# 5VRegulator.net
KiCad netlist of a schematic drawn in Altium Designer
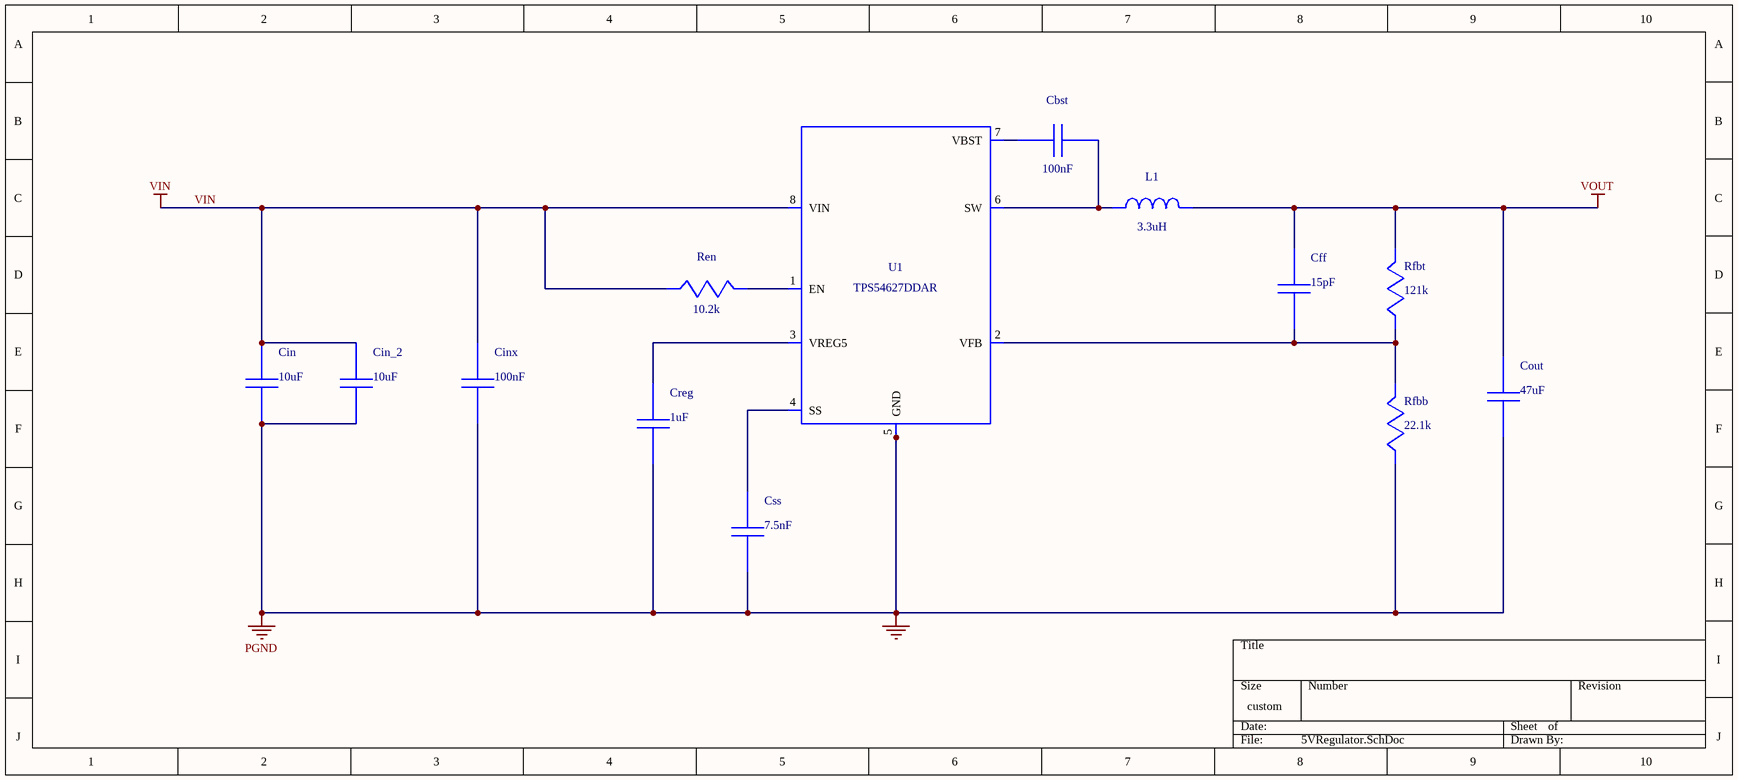
[diagram p0: 5VRegulator.SchDoc]

(export (version "E")
  (design (tool "Eeschema 10.0.6"))
  (components
    (comp (ref "Cbst")
      (value "100nF")
      (description "06033C104KAT2A")
      (libsource (lib "TI WEBENCH") (part "Cbst"))
    )
    (comp (ref "Cff")
      (value "15pF")
      (description "C0603C150M8GACTU")
      (libsource (lib "TI WEBENCH") (part "Cff"))
    )
    (comp (ref "Cin")
      (value "10uF")
      (description "GRM31CR71E106KA1")
      (fields (field (name "MANUFACTURER PART NUMBER") "GRM31CR71E106KA12L"))
      (libsource (lib "TI WEBENCH") (part "Cin"))
    )
    (comp (ref "Cinx")
      (value "100nF")
      (description "06033C104KAT2A")
      (libsource (lib "TI WEBENCH") (part "Cinx"))
    )
    (comp (ref "Cin_2")
      (value "10uF")
      (description "GRM31CR71E106KA1")
      (fields (field (name "MANUFACTURER PART NUMBER") "GRM31CR71E106KA12L"))
      (libsource (lib "TI WEBENCH") (part "Cin_2"))
    )
    (comp (ref "Cout")
      (value "47uF")
      (description "GRM31CR61A476KE1")
      (fields (field (name "MANUFACTURER PART NUMBER") "GRM31CR61A476KE15L"))
      (libsource (lib "TI WEBENCH") (part "Cout"))
    )
    (comp (ref "Creg")
      (value "1uF")
      (description "C0603C105Z8VACTU")
      (libsource (lib "TI WEBENCH") (part "Creg"))
    )
    (comp (ref "Css")
      (value "7.5nF")
      (description "C0603C752J3GAC78")
      (fields (field (name "MANUFACTURER PART NUMBER") "C0603C752J3GAC7867"))
      (libsource (lib "TI WEBENCH") (part "Css"))
    )
    (comp (ref "L1") (value "3.3uH") (description "SRP1040-3R3M") (libsource (lib "TI WEBENCH") (part "L1")))
    (comp (ref "Ren")
      (value "10.2k")
      (description "CRCW040210K2FKED")
      (libsource (lib "TI WEBENCH") (part "Ren"))
    )
    (comp (ref "Rfbb")
      (value "22.1k")
      (description "CRCW040222K1FKED")
      (libsource (lib "TI WEBENCH") (part "Rfbb"))
    )
    (comp (ref "Rfbt")
      (value "121k")
      (description "CRCW0402121KFKED")
      (libsource (lib "TI WEBENCH") (part "Rfbt"))
    )
    (comp (ref "U1")
      (value "TPS54627DDA")
      (description "TPS54627DDAR")
      (fields (field (name "PACKAGEREFERENCE") "TPS54627DDAR"))
      (libsource (lib "TI WEBENCH") (part "U1"))
    )
  )
  (nets
    (net (code "1") (name "0") (class "Default")
      (node (ref "Cin") (pin "2") (pinfunction "2_2") (pintype "passive"))
      (node (ref "Cin_2") (pin "2") (pinfunction "2_2") (pintype "passive"))
      (node (ref "Cinx") (pin "2") (pinfunction "2_2") (pintype "passive"))
      (node (ref "Cout") (pin "2") (pinfunction "2_2") (pintype "passive"))
      (node (ref "Creg") (pin "2") (pinfunction "2_2") (pintype "passive"))
      (node (ref "Css") (pin "2") (pinfunction "2_2") (pintype "passive"))
      (node (ref "Rfbb") (pin "2") (pinfunction "2_2") (pintype "passive"))
      (node (ref "U1") (pin "5") (pinfunction "GND_5") (pintype "passive"))
      (node (ref "U1") (pin "9") (pinfunction "ETPAD_9") (pintype "passive"))
    )
    (net (code "2") (name "Net-(U1-EN)") (class "Default")
      (node (ref "Ren") (pin "1") (pinfunction "1_1") (pintype "passive"))
      (node (ref "U1") (pin "1") (pinfunction "EN_1") (pintype "passive"))
    )
    (net (code "3") (name "Net-(U1-SS)") (class "Default")
      (node (ref "Css") (pin "1") (pinfunction "1_1") (pintype "passive"))
      (node (ref "U1") (pin "4") (pinfunction "SS_4") (pintype "passive"))
    )
    (net (code "4") (name "Net-(U1-SW)") (class "Default")
      (node (ref "Cbst") (pin "2") (pinfunction "2_2") (pintype "passive"))
      (node (ref "L1") (pin "1") (pinfunction "1_1") (pintype "passive"))
      (node (ref "U1") (pin "6") (pinfunction "SW_6") (pintype "passive"))
    )
    (net (code "5") (name "Net-(U1-VBST)") (class "Default")
      (node (ref "Cbst") (pin "1") (pinfunction "1_1") (pintype "passive"))
      (node (ref "U1") (pin "7") (pinfunction "VBST_7") (pintype "passive"))
    )
    (net (code "6") (name "Net-(U1-VFB)") (class "Default")
      (node (ref "Cff") (pin "2") (pinfunction "2_2") (pintype "passive"))
      (node (ref "Rfbb") (pin "1") (pinfunction "1_1") (pintype "passive"))
      (node (ref "Rfbt") (pin "2") (pinfunction "2_2") (pintype "passive"))
      (node (ref "U1") (pin "2") (pinfunction "VFB_2") (pintype "passive"))
    )
    (net (code "7") (name "Net-(U1-VREG5)") (class "Default")
      (node (ref "Creg") (pin "1") (pinfunction "1_1") (pintype "passive"))
      (node (ref "U1") (pin "3") (pinfunction "VREG5_3") (pintype "passive"))
    )
    (net (code "8") (name "VIN") (class "Default")
      (node (ref "Cin") (pin "1") (pinfunction "1_1") (pintype "passive"))
      (node (ref "Cin_2") (pin "1") (pinfunction "1_1") (pintype "passive"))
      (node (ref "Cinx") (pin "1") (pinfunction "1_1") (pintype "passive"))
      (node (ref "Ren") (pin "2") (pinfunction "2_2") (pintype "passive"))
      (node (ref "U1") (pin "8") (pinfunction "VIN_8") (pintype "passive"))
    )
    (net (code "9") (name "VOUT") (class "Default")
      (node (ref "Cff") (pin "1") (pinfunction "1_1") (pintype "passive"))
      (node (ref "Cout") (pin "1") (pinfunction "1_1") (pintype "passive"))
      (node (ref "L1") (pin "2") (pinfunction "2_2") (pintype "passive"))
      (node (ref "Rfbt") (pin "1") (pinfunction "1_1") (pintype "passive"))
    )
  )
)
